# IEEE-802_15_4.net
KiCad netlist of a schematic drawn in Altium Designer
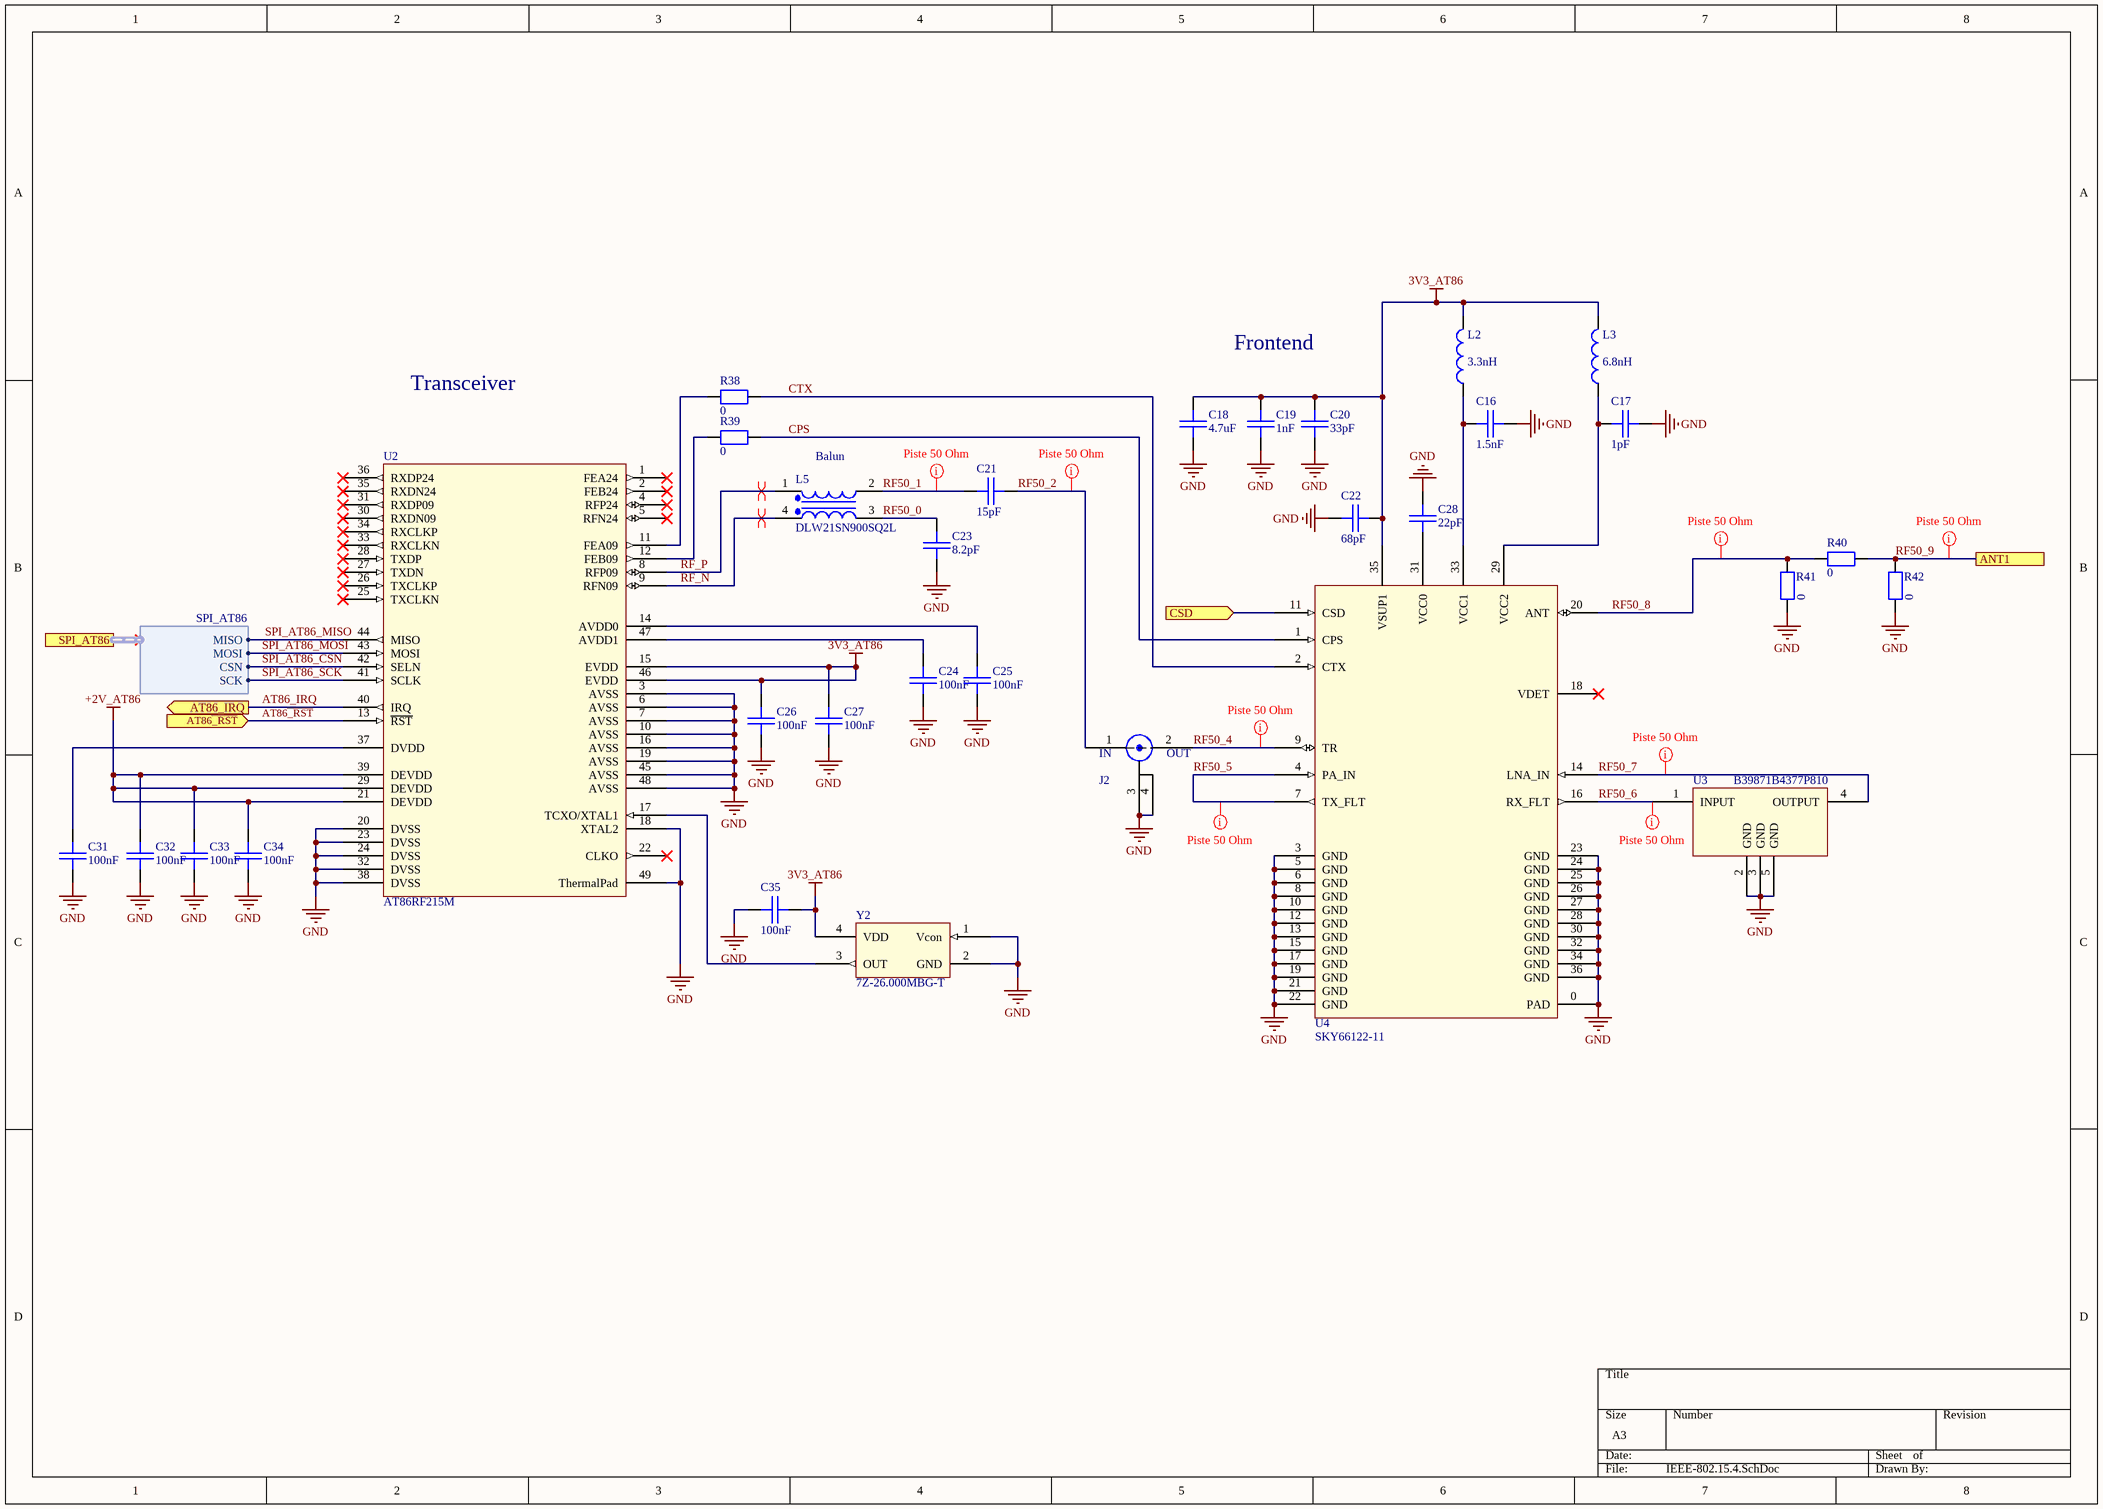
[diagram p0: IEEE-802.15.4.SchDoc]

(export (version "E")
  (design (tool "Eeschema 10.0.6"))
  (components
    (comp (ref "C16")
      (value "1.5nF")
      (footprint "SM/C_0402")
      (fields (field (name "Comment") "C-1nF-0402"))
      (libsource (lib "IEEE-802.15.4") (part "C-1.5nF-0402"))
    )
    (comp (ref "C17")
      (value "1pF")
      (footprint "SM/C_0402")
      (fields (field (name "Comment") "C-1pF-0402"))
      (libsource (lib "IEEE-802.15.4") (part "C-1pF-0402"))
    )
    (comp (ref "C18")
      (value "4.7uF")
      (footprint "SM/C_0603")
      (fields
        (field (name "VOLTAGE") "6.3V")
        (field (name "TOLERANCE") "10%")
        (field (name "Comment") "C-4.7uF-0603")
      )
      (libsource (lib "IEEE-802.15.4") (part "C-4.7uF-0603"))
    )
    (comp (ref "C19")
      (value "1nF")
      (footprint "SM/C_0402")
      (fields
        (field (name "VOLTAGE") "50V")
        (field (name "TOLERANCE") "1%")
        (field (name "Comment") "C-1nF-0402")
      )
      (libsource (lib "IEEE-802.15.4") (part "C-1nF-0402"))
    )
    (comp (ref "C20")
      (value "33pF")
      (footprint "SM/C_0402")
      (fields
        (field (name "VOLTAGE") "50V")
        (field (name "TOLERANCE") "5%")
        (field (name "Comment") "C-33pF-0402")
      )
      (libsource (lib "IEEE-802.15.4") (part "C-33pF-0402"))
    )
    (comp (ref "C21")
      (value "15pF")
      (footprint "TB_Module_RF_OFDM:SM/C_0402")
      (fields
        (field (name "VOLTAGE") "6.3V")
        (field (name "TOLERANCE") "10%")
        (field (name "Comment") "C-15pF-0402")
      )
      (libsource (lib "TB_Module_RF_OFDM") (part "C-15pF-0402"))
    )
    (comp (ref "C22")
      (value "68pF")
      (footprint "SM/C_0402")
      (fields
        (field (name "VOLTAGE") "50V")
        (field (name "TOLERANCE") "5%")
        (field (name "Comment") "C-68pF-0402")
      )
      (libsource (lib "IEEE-802.15.4") (part "C-68pF-0402"))
    )
    (comp (ref "C23")
      (value "8.2pF")
      (footprint "TB_Module_RF_OFDM:SM/C_0402")
      (fields
        (field (name "VOLTAGE") "6.3V")
        (field (name "TOLERANCE") "10%")
        (field (name "Comment") "C-8.2pF-0402")
      )
      (libsource (lib "TB_Module_RF_OFDM") (part "C-8.2pF-0402"))
    )
    (comp (ref "C24")
      (value "100nF")
      (footprint "TB_Module_RF_OFDM:SM/C_0402")
      (fields
        (field (name "VOLTAGE") "25V")
        (field (name "TOLERANCE") "10%")
        (field (name "Comment") "C-100nF-0402")
      )
      (libsource (lib "TB_Module_RF_OFDM") (part "C-100nF-0402"))
    )
    (comp (ref "C25")
      (value "100nF")
      (footprint "TB_Module_RF_OFDM:SM/C_0402")
      (fields
        (field (name "VOLTAGE") "25V")
        (field (name "TOLERANCE") "10%")
        (field (name "Comment") "C-100nF-0402")
      )
      (libsource (lib "TB_Module_RF_OFDM") (part "C-100nF-0402"))
    )
    (comp (ref "C26")
      (value "100nF")
      (footprint "TB_Module_RF_OFDM:SM/C_0402")
      (fields
        (field (name "VOLTAGE") "25V")
        (field (name "TOLERANCE") "10%")
        (field (name "Comment") "C-100nF-0402")
      )
      (libsource (lib "TB_Module_RF_OFDM") (part "C-100nF-0402"))
    )
    (comp (ref "C27")
      (value "100nF")
      (footprint "TB_Module_RF_OFDM:SM/C_0402")
      (fields
        (field (name "VOLTAGE") "25V")
        (field (name "TOLERANCE") "10%")
        (field (name "Comment") "C-100nF-0402")
      )
      (libsource (lib "TB_Module_RF_OFDM") (part "C-100nF-0402"))
    )
    (comp (ref "C28")
      (value "22pF")
      (footprint "SM/C_0402")
      (fields
        (field (name "VOLTAGE") "50V")
        (field (name "TOLERANCE") "1%")
        (field (name "Comment") "C-22pF-0402")
      )
      (libsource (lib "IEEE-802.15.4") (part "C-22pF-0402"))
    )
    (comp (ref "C31")
      (value "100nF")
      (footprint "TB_Module_RF_OFDM:SM/C_0402")
      (fields
        (field (name "VOLTAGE") "25V")
        (field (name "TOLERANCE") "10%")
        (field (name "Comment") "C-100nF-0402")
      )
      (libsource (lib "TB_Module_RF_OFDM") (part "C-100nF-0402"))
    )
    (comp (ref "C32")
      (value "100nF")
      (footprint "TB_Module_RF_OFDM:SM/C_0402")
      (fields
        (field (name "VOLTAGE") "25V")
        (field (name "TOLERANCE") "10%")
        (field (name "Comment") "C-100nF-0402")
      )
      (libsource (lib "TB_Module_RF_OFDM") (part "C-100nF-0402"))
    )
    (comp (ref "C33")
      (value "100nF")
      (footprint "TB_Module_RF_OFDM:SM/C_0402")
      (fields
        (field (name "VOLTAGE") "25V")
        (field (name "TOLERANCE") "10%")
        (field (name "Comment") "C-100nF-0402")
      )
      (libsource (lib "TB_Module_RF_OFDM") (part "C-100nF-0402"))
    )
    (comp (ref "C34")
      (value "100nF")
      (footprint "TB_Module_RF_OFDM:SM/C_0402")
      (fields
        (field (name "VOLTAGE") "25V")
        (field (name "TOLERANCE") "10%")
        (field (name "Comment") "C-100nF-0402")
      )
      (libsource (lib "TB_Module_RF_OFDM") (part "C-100nF-0402"))
    )
    (comp (ref "C35")
      (value "100nF")
      (footprint "TB_Module_RF_OFDM:SM/C_0402")
      (fields
        (field (name "VOLTAGE") "25V")
        (field (name "TOLERANCE") "10%")
        (field (name "Comment") "C-100nF-0402")
      )
      (libsource (lib "TB_Module_RF_OFDM") (part "C-100nF-0402"))
    )
    (comp (ref "J2")
      (value "MM8930-2620RJ4")
      (footprint "MM8030-2610RJ3")
      (description "SWG Connecteur Socle, prise femelle 50Ohms")
      (libsource (lib "IEEE-802.15.4") (part "MM8030-2610RJ3"))
    )
    (comp (ref "L2")
      (value "3.3nH")
      (footprint "SM/L_0402")
      (fields (field (name "TOLERANCE") "0.3nH") (field (name "Comment") "L-3.3nH-0402"))
      (libsource (lib "IEEE-802.15.4") (part "L-3.3nH-0402"))
    )
    (comp (ref "L3")
      (value "6.8nH")
      (footprint "SM/L_0603 (1608)")
      (fields (field (name "TOLERANCE") "5%") (field (name "Comment") "L-6.8nH-0603"))
      (libsource (lib "IEEE-802.15.4") (part "L-6.8nH-0603"))
    )
    (comp (ref "L5")
      (value "DLW21SN900SQ2L")
      (footprint "MURA-DLW21SN900SQ2L-4_V")
      (description "Chip Common Mode Choke Coil, 90 Ohm, 330 mA, -40 to 85 degC, 4-Pin SMD, RoHS, Tape and Reel")
      (fields (field (name "MANUFACTURER") "Murata"))
      (libsource (lib "TB_Module_RF_OFDM") (part "DLW21SN900SQ2L"))
    )
    (comp (ref "R38")
      (value "0")
      (footprint "SM/R_0402")
      (fields (field (name "TOLERANCE") "1%") (field (name "Comment") "R-0-0402"))
      (libsource (lib "TB_Module_RF_OFDM") (part "R-0-0402"))
    )
    (comp (ref "R39")
      (value "0")
      (footprint "SM/R_0402")
      (fields (field (name "TOLERANCE") "1%") (field (name "Comment") "R-0-0402"))
      (libsource (lib "TB_Module_RF_OFDM") (part "R-0-0402"))
    )
    (comp (ref "R40")
      (value "0")
      (footprint "SM/R_0402")
      (fields (field (name "TOLERANCE") "1%") (field (name "Comment") "R-0-0402"))
      (libsource (lib "TB_Module_RF_OFDM") (part "R-0-0402"))
    )
    (comp (ref "R41")
      (value "0")
      (footprint "SM/R_0402")
      (fields (field (name "TOLERANCE") "1%") (field (name "Comment") "R-0-0402"))
      (libsource (lib "TB_Module_RF_OFDM") (part "R-0-0402"))
    )
    (comp (ref "R42")
      (value "0")
      (footprint "SM/R_0402")
      (fields (field (name "TOLERANCE") "1%") (field (name "Comment") "R-0-0402"))
      (libsource (lib "TB_Module_RF_OFDM") (part "R-0-0402"))
    )
    (comp (ref "U2")
      (value "AT86RF215M")
      (footprint "QFN50P700X700X90-49N-D")
      (description "IC RF TXRX 802.15.4/ISM 48-VFQFN")
      (libsource (lib "TB_Module_RF_OFDM") (part "AT86RF215M"))
    )
    (comp (ref "U3")
      (value "B39871B4377P810")
      (footprint "B39871B4377P810")
      (libsource (lib "IEEE-802.15.4") (part "B39871B4377P810"))
    )
    (comp (ref "U4")
      (value "SKY66122-11")
      (footprint "SKY66122-11")
      (libsource (lib "IEEE-802.15.4") (part "SKY66122-11"))
    )
    (comp (ref "Y2")
      (value "7Z-26.000MBG-T")
      (footprint "7Z-26.000MBG-T")
      (description "XTAL OSC TCXO 26.0000MHZ SNWV")
      (libsource (lib "IEEE-802.15.4") (part "7Z-26.000MBG-T"))
    )
  )
  (nets
    (net (code "2") (name "+2V_AT86") (class "Default")
      (node (ref "C32") (pin "2") (pinfunction "2_2") (pintype "passive"))
      (node (ref "C33") (pin "2") (pinfunction "2_2") (pintype "passive"))
      (node (ref "C34") (pin "2") (pinfunction "2_2") (pintype "passive"))
      (node (ref "U2") (pin "21") (pinfunction "DEVDD_21") (pintype "power_in"))
      (node (ref "U2") (pin "29") (pinfunction "DEVDD_29") (pintype "power_in"))
      (node (ref "U2") (pin "39") (pinfunction "DEVDD_39") (pintype "power_in"))
    )
    (net (code "3") (name "/AT86_IRQ") (class "Default")
      (node (ref "U2") (pin "40") (pinfunction "IRQ_40") (pintype "output"))
    )
    (net (code "4") (name "/AT86~{_RST}") (class "Default")
      (node (ref "U2") (pin "13") (pinfunction "~{RST}_13") (pintype "input"))
    )
    (net (code "5") (name "/CPS") (class "Default")
      (node (ref "R39") (pin "2") (pinfunction "2_2") (pintype "passive"))
      (node (ref "U4") (pin "1") (pinfunction "CPS_1") (pintype "input"))
    )
    (net (code "6") (name "/CSD") (class "Default")
      (node (ref "U4") (pin "11") (pinfunction "CSD_11") (pintype "input"))
    )
    (net (code "7") (name "/CTX") (class "Default")
      (node (ref "R38") (pin "2") (pinfunction "2_2") (pintype "passive"))
      (node (ref "U4") (pin "2") (pinfunction "CTX_2") (pintype "input"))
    )
    (net (code "8") (name "/RF50_0") (class "Default")
      (node (ref "C23") (pin "2") (pinfunction "2_2") (pintype "passive"))
      (node (ref "L5") (pin "3") (pinfunction "3_3") (pintype "passive"))
    )
    (net (code "9") (name "/RF50_1") (class "Default")
      (node (ref "C21") (pin "1") (pinfunction "1_1") (pintype "passive"))
      (node (ref "L5") (pin "2") (pinfunction "2_2") (pintype "passive"))
    )
    (net (code "10") (name "/RF50_2") (class "Default")
      (node (ref "C21") (pin "2") (pinfunction "2_2") (pintype "passive"))
      (node (ref "J2") (pin "1") (pinfunction "IN_1") (pintype "passive"))
    )
    (net (code "11") (name "/RF50_4") (class "Default")
      (node (ref "J2") (pin "2") (pinfunction "IN_2") (pintype "passive"))
      (node (ref "U4") (pin "9") (pinfunction "TR_9") (pintype "bidirectional"))
    )
    (net (code "12") (name "/RF50_5") (class "Default")
      (node (ref "U4") (pin "4") (pinfunction "PA_IN_4") (pintype "input"))
      (node (ref "U4") (pin "7") (pinfunction "TX_FLT_7") (pintype "output"))
    )
    (net (code "13") (name "/RF50_6") (class "Default")
      (node (ref "U3") (pin "1") (pinfunction "INPUT_1") (pintype "passive"))
      (node (ref "U4") (pin "16") (pinfunction "RX_FLT_16") (pintype "output"))
    )
    (net (code "14") (name "/RF50_7") (class "Default")
      (node (ref "U3") (pin "4") (pinfunction "OUTPUT_4") (pintype "passive"))
      (node (ref "U4") (pin "14") (pinfunction "LNA_IN_14") (pintype "input"))
    )
    (net (code "15") (name "/RF50_8") (class "Default")
      (node (ref "R40") (pin "1") (pinfunction "1_1") (pintype "passive"))
      (node (ref "R41") (pin "2") (pinfunction "2_2") (pintype "passive"))
      (node (ref "U4") (pin "20") (pinfunction "ANT_20") (pintype "bidirectional"))
    )
    (net (code "16") (name "/RF50_9") (class "Default")
      (node (ref "R40") (pin "2") (pinfunction "2_2") (pintype "passive"))
      (node (ref "R42") (pin "2") (pinfunction "2_2") (pintype "passive"))
    )
    (net (code "17") (name "/RF_N") (class "Default")
      (node (ref "L5") (pin "4") (pinfunction "4_4") (pintype "passive"))
      (node (ref "U2") (pin "9") (pinfunction "RFN09_9") (pintype "bidirectional"))
    )
    (net (code "18") (name "/RF_P") (class "Default")
      (node (ref "L5") (pin "1") (pinfunction "1_1") (pintype "passive"))
      (node (ref "U2") (pin "8") (pinfunction "RFP09_8") (pintype "bidirectional"))
    )
    (net (code "19") (name "/SPI_AT86_CSN") (class "Default")
      (node (ref "U2") (pin "42") (pinfunction "SELN_42") (pintype "input"))
    )
    (net (code "20") (name "/SPI_AT86_MISO") (class "Default")
      (node (ref "U2") (pin "44") (pinfunction "MISO_44") (pintype "output"))
    )
    (net (code "21") (name "/SPI_AT86_MOSI") (class "Default")
      (node (ref "U2") (pin "43") (pinfunction "MOSI_43") (pintype "input"))
    )
    (net (code "22") (name "/SPI_AT86_SCK") (class "Default")
      (node (ref "U2") (pin "41") (pinfunction "SCLK_41") (pintype "input"))
    )
    (net (code "24") (name "3V3_AT86") (class "Default")
      (node (ref "C18") (pin "2") (pinfunction "2_2") (pintype "passive"))
      (node (ref "C19") (pin "2") (pinfunction "2_2") (pintype "passive"))
      (node (ref "C20") (pin "2") (pinfunction "2_2") (pintype "passive"))
      (node (ref "C22") (pin "2") (pinfunction "2_2") (pintype "passive"))
      (node (ref "C26") (pin "2") (pinfunction "2_2") (pintype "passive"))
      (node (ref "C27") (pin "2") (pinfunction "2_2") (pintype "passive"))
      (node (ref "C35") (pin "1") (pinfunction "1_1") (pintype "passive"))
      (node (ref "L2") (pin "2") (pinfunction "2_2") (pintype "passive"))
      (node (ref "L3") (pin "2") (pinfunction "2_2") (pintype "passive"))
      (node (ref "U2") (pin "15") (pinfunction "EVDD_15") (pintype "power_in"))
      (node (ref "U2") (pin "46") (pinfunction "EVDD_46") (pintype "power_in"))
      (node (ref "U4") (pin "35") (pinfunction "VSUP1_35") (pintype "power_in"))
      (node (ref "Y2") (pin "4") (pinfunction "VDD_4") (pintype "power_in"))
    )
    (net (code "25") (name "GND") (class "Default")
      (node (ref "C16") (pin "2") (pinfunction "2_2") (pintype "passive"))
      (node (ref "C17") (pin "2") (pinfunction "2_2") (pintype "passive"))
      (node (ref "C18") (pin "1") (pinfunction "1_1") (pintype "passive"))
      (node (ref "C19") (pin "1") (pinfunction "1_1") (pintype "passive"))
      (node (ref "C20") (pin "1") (pinfunction "1_1") (pintype "passive"))
      (node (ref "C22") (pin "1") (pinfunction "1_1") (pintype "passive"))
      (node (ref "C23") (pin "1") (pinfunction "1_1") (pintype "passive"))
      (node (ref "C24") (pin "1") (pinfunction "1_1") (pintype "passive"))
      (node (ref "C25") (pin "1") (pinfunction "1_1") (pintype "passive"))
      (node (ref "C26") (pin "1") (pinfunction "1_1") (pintype "passive"))
      (node (ref "C27") (pin "1") (pinfunction "1_1") (pintype "passive"))
      (node (ref "C28") (pin "2") (pinfunction "2_2") (pintype "passive"))
      (node (ref "C31") (pin "1") (pinfunction "1_1") (pintype "passive"))
      (node (ref "C32") (pin "1") (pinfunction "1_1") (pintype "passive"))
      (node (ref "C33") (pin "1") (pinfunction "1_1") (pintype "passive"))
      (node (ref "C34") (pin "1") (pinfunction "1_1") (pintype "passive"))
      (node (ref "C35") (pin "2") (pinfunction "2_2") (pintype "passive"))
      (node (ref "J2") (pin "3") (pinfunction "GND_3") (pintype "passive"))
      (node (ref "J2") (pin "4") (pinfunction "GND_4") (pintype "passive"))
      (node (ref "R41") (pin "1") (pinfunction "1_1") (pintype "passive"))
      (node (ref "R42") (pin "1") (pinfunction "1_1") (pintype "passive"))
      (node (ref "U2") (pin "10") (pinfunction "AVSS_10") (pintype "power_in"))
      (node (ref "U2") (pin "16") (pinfunction "AVSS_16") (pintype "power_in"))
      (node (ref "U2") (pin "18") (pinfunction "XTAL2_18") (pintype "passive"))
      (node (ref "U2") (pin "19") (pinfunction "AVSS_19") (pintype "power_in"))
      (node (ref "U2") (pin "20") (pinfunction "DVSS_20") (pintype "power_in"))
      (node (ref "U2") (pin "23") (pinfunction "DVSS_23") (pintype "power_in"))
      (node (ref "U2") (pin "24") (pinfunction "DVSS_24") (pintype "power_in"))
      (node (ref "U2") (pin "3") (pinfunction "AVSS_3") (pintype "power_in"))
      (node (ref "U2") (pin "32") (pinfunction "DVSS_32") (pintype "power_in"))
      (node (ref "U2") (pin "38") (pinfunction "DVSS_38") (pintype "power_in"))
      (node (ref "U2") (pin "45") (pinfunction "AVSS_45") (pintype "power_in"))
      (node (ref "U2") (pin "48") (pinfunction "AVSS_48") (pintype "power_in"))
      (node (ref "U2") (pin "49") (pinfunction "ThermalPad_49") (pintype "passive"))
      (node (ref "U2") (pin "6") (pinfunction "AVSS_6") (pintype "power_in"))
      (node (ref "U2") (pin "7") (pinfunction "AVSS_7") (pintype "power_in"))
      (node (ref "U3") (pin "2") (pinfunction "GND_2") (pintype "passive"))
      (node (ref "U3") (pin "3") (pinfunction "GND_3") (pintype "passive"))
      (node (ref "U3") (pin "5") (pinfunction "GND_5") (pintype "passive"))
      (node (ref "U4") (pin "0") (pinfunction "PAD_0") (pintype "power_in"))
      (node (ref "U4") (pin "10") (pinfunction "GND_10") (pintype "passive"))
      (node (ref "U4") (pin "12") (pinfunction "GND_12") (pintype "passive"))
      (node (ref "U4") (pin "13") (pinfunction "GND_13") (pintype "passive"))
      (node (ref "U4") (pin "15") (pinfunction "GND_15") (pintype "passive"))
      (node (ref "U4") (pin "17") (pinfunction "GND_17") (pintype "passive"))
      (node (ref "U4") (pin "19") (pinfunction "GND_19") (pintype "passive"))
      (node (ref "U4") (pin "21") (pinfunction "GND_21") (pintype "passive"))
      (node (ref "U4") (pin "22") (pinfunction "GND_22") (pintype "power_in"))
      (node (ref "U4") (pin "23") (pinfunction "GND_23") (pintype "power_in"))
      (node (ref "U4") (pin "24") (pinfunction "GND_24") (pintype "power_in"))
      (node (ref "U4") (pin "25") (pinfunction "GND_25") (pintype "power_in"))
      (node (ref "U4") (pin "26") (pinfunction "GND_26") (pintype "power_in"))
      (node (ref "U4") (pin "27") (pinfunction "GND_27") (pintype "power_in"))
      (node (ref "U4") (pin "28") (pinfunction "GND_28") (pintype "power_in"))
      (node (ref "U4") (pin "3") (pinfunction "GND_3") (pintype "power_in"))
      (node (ref "U4") (pin "30") (pinfunction "GND_30") (pintype "power_in"))
      (node (ref "U4") (pin "32") (pinfunction "GND_32") (pintype "power_in"))
      (node (ref "U4") (pin "34") (pinfunction "GND_34") (pintype "power_in"))
      (node (ref "U4") (pin "36") (pinfunction "GND_36") (pintype "power_in"))
      (node (ref "U4") (pin "5") (pinfunction "GND_5") (pintype "power_in"))
      (node (ref "U4") (pin "6") (pinfunction "GND_6") (pintype "power_in"))
      (node (ref "U4") (pin "8") (pinfunction "GND_8") (pintype "power_in"))
      (node (ref "Y2") (pin "1") (pinfunction "Vcon_1") (pintype "input"))
      (node (ref "Y2") (pin "2") (pinfunction "GND_2") (pintype "power_in"))
    )
    (net (code "26") (name "Net-(U2-AVDD0)") (class "Default")
      (node (ref "C25") (pin "2") (pinfunction "2_2") (pintype "passive"))
      (node (ref "U2") (pin "14") (pinfunction "AVDD0_14") (pintype "power_in"))
    )
    (net (code "27") (name "Net-(U2-AVDD1)") (class "Default")
      (node (ref "C24") (pin "2") (pinfunction "2_2") (pintype "passive"))
      (node (ref "U2") (pin "47") (pinfunction "AVDD1_47") (pintype "power_in"))
    )
    (net (code "28") (name "Net-(U2-DVDD)") (class "Default")
      (node (ref "C31") (pin "2") (pinfunction "2_2") (pintype "passive"))
      (node (ref "U2") (pin "37") (pinfunction "DVDD_37") (pintype "power_in"))
    )
    (net (code "29") (name "Net-(U2-FEA09)") (class "Default")
      (node (ref "R38") (pin "1") (pinfunction "1_1") (pintype "passive"))
      (node (ref "U2") (pin "11") (pinfunction "FEA09_11") (pintype "output"))
    )
    (net (code "30") (name "Net-(U2-FEB09)") (class "Default")
      (node (ref "R39") (pin "1") (pinfunction "1_1") (pintype "passive"))
      (node (ref "U2") (pin "12") (pinfunction "FEB09_12") (pintype "output"))
    )
    (net (code "31") (name "Net-(U2-TCXO{slash}XTAL1)") (class "Default")
      (node (ref "U2") (pin "17") (pinfunction "TCXO/XTAL1_17") (pintype "input"))
      (node (ref "Y2") (pin "3") (pinfunction "OUT_3") (pintype "output"))
    )
    (net (code "32") (name "Net-(U4-VCC0)") (class "Default")
      (node (ref "C28") (pin "1") (pinfunction "1_1") (pintype "passive"))
      (node (ref "U4") (pin "31") (pinfunction "VCC0_31") (pintype "power_in"))
    )
    (net (code "33") (name "Net-(U4-VCC1)") (class "Default")
      (node (ref "C16") (pin "1") (pinfunction "1_1") (pintype "passive"))
      (node (ref "L2") (pin "1") (pinfunction "1_1") (pintype "passive"))
      (node (ref "U4") (pin "33") (pinfunction "VCC1_33") (pintype "power_in"))
    )
    (net (code "34") (name "Net-(U4-VCC2)") (class "Default")
      (node (ref "C17") (pin "1") (pinfunction "1_1") (pintype "passive"))
      (node (ref "L3") (pin "1") (pinfunction "1_1") (pintype "passive"))
      (node (ref "U4") (pin "29") (pinfunction "VCC2_29") (pintype "power_in"))
    )
    (net (code "35") (name "unconnected-(U2-CLKO-Pad22)") (class "Default")
      (node (ref "U2") (pin "22") (pinfunction "CLKO_22") (pintype "output+no_connect"))
    )
    (net (code "36") (name "unconnected-(U2-FEA24-Pad1)") (class "Default")
      (node (ref "U2") (pin "1") (pinfunction "FEA24_1") (pintype "output+no_connect"))
    )
    (net (code "37") (name "unconnected-(U2-FEB24-Pad2)") (class "Default")
      (node (ref "U2") (pin "2") (pinfunction "FEB24_2") (pintype "output+no_connect"))
    )
    (net (code "38") (name "unconnected-(U2-RFN24-Pad5)") (class "Default")
      (node (ref "U2") (pin "5") (pinfunction "RFN24_5") (pintype "bidirectional+no_connect"))
    )
    (net (code "39") (name "unconnected-(U2-RFP24-Pad4)") (class "Default")
      (node (ref "U2") (pin "4") (pinfunction "RFP24_4") (pintype "bidirectional+no_connect"))
    )
    (net (code "40") (name "unconnected-(U2-RXCLKN-Pad33)") (class "Default")
      (node (ref "U2") (pin "33") (pinfunction "RXCLKN_33") (pintype "output+no_connect"))
    )
    (net (code "41") (name "unconnected-(U2-RXCLKP-Pad34)") (class "Default")
      (node (ref "U2") (pin "34") (pinfunction "RXCLKP_34") (pintype "output+no_connect"))
    )
    (net (code "42") (name "unconnected-(U2-RXDN09-Pad30)") (class "Default")
      (node (ref "U2") (pin "30") (pinfunction "RXDN09_30") (pintype "output+no_connect"))
    )
    (net (code "43") (name "unconnected-(U2-RXDN24-Pad35)") (class "Default")
      (node (ref "U2") (pin "35") (pinfunction "RXDN24_35") (pintype "output+no_connect"))
    )
    (net (code "44") (name "unconnected-(U2-RXDP09-Pad31)") (class "Default")
      (node (ref "U2") (pin "31") (pinfunction "RXDP09_31") (pintype "output+no_connect"))
    )
    (net (code "45") (name "unconnected-(U2-RXDP24-Pad36)") (class "Default")
      (node (ref "U2") (pin "36") (pinfunction "RXDP24_36") (pintype "output+no_connect"))
    )
    (net (code "46") (name "unconnected-(U2-TXCLKN-Pad25)") (class "Default")
      (node (ref "U2") (pin "25") (pinfunction "TXCLKN_25") (pintype "input+no_connect"))
    )
    (net (code "47") (name "unconnected-(U2-TXCLKP-Pad26)") (class "Default")
      (node (ref "U2") (pin "26") (pinfunction "TXCLKP_26") (pintype "input+no_connect"))
    )
    (net (code "48") (name "unconnected-(U2-TXDN-Pad27)") (class "Default")
      (node (ref "U2") (pin "27") (pinfunction "TXDN_27") (pintype "input+no_connect"))
    )
    (net (code "49") (name "unconnected-(U2-TXDP-Pad28)") (class "Default")
      (node (ref "U2") (pin "28") (pinfunction "TXDP_28") (pintype "input+no_connect"))
    )
    (net (code "50") (name "unconnected-(U4-VDET-Pad18)") (class "Default")
      (node (ref "U4") (pin "18") (pinfunction "VDET_18") (pintype "power_in+no_connect"))
    )
  )
)
